# Switch_Board.net
KiCad netlist of a schematic drawn in EAGLE
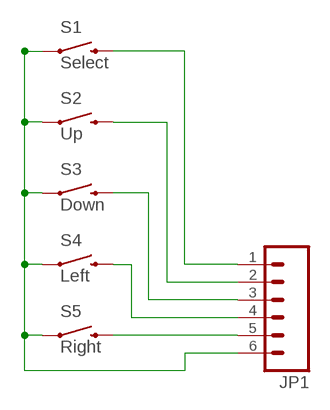
[diagram p0: schematic, sheet 1]

(export (version "E")
  (design (tool "Eeschema 10.0.6"))
  (components
    (comp (ref "JP1")
      (value "M06SMD-1MM")
      (footprint "eagle-import:1X06-1MM")
      (libsource (lib "eagle-import") (part "M06SMD-1MM"))
    )
    (comp (ref "S1")
      (value "Select")
      (footprint "eagle-import:TACTILE-SWITCH-SMD")
      (libsource (lib "eagle-import") (part "SWITCH-MOMENTARY-2SMD"))
    )
    (comp (ref "S2")
      (value "Up")
      (footprint "eagle-import:TACTILE-SWITCH-SMD")
      (libsource (lib "eagle-import") (part "SWITCH-MOMENTARY-2SMD"))
    )
    (comp (ref "S3")
      (value "Down")
      (footprint "eagle-import:TACTILE-SWITCH-SMD")
      (libsource (lib "eagle-import") (part "SWITCH-MOMENTARY-2SMD"))
    )
    (comp (ref "S4")
      (value "Left")
      (footprint "eagle-import:TACTILE-SWITCH-SMD")
      (libsource (lib "eagle-import") (part "SWITCH-MOMENTARY-2SMD"))
    )
    (comp (ref "S5")
      (value "Right")
      (footprint "eagle-import:TACTILE-SWITCH-SMD")
      (libsource (lib "eagle-import") (part "SWITCH-MOMENTARY-2SMD"))
    )
  )
  (nets
    (net (code "1") (name "Net-(JP1-Pad6)") (class "Default")
      (node (ref "JP1") (pin "6") (pinfunction "6_6") (pintype "passive"))
      (node (ref "S1") (pin "1") (pinfunction "1_1") (pintype "passive"))
      (node (ref "S2") (pin "1") (pinfunction "1_1") (pintype "passive"))
      (node (ref "S3") (pin "1") (pinfunction "1_1") (pintype "passive"))
      (node (ref "S4") (pin "1") (pinfunction "1_1") (pintype "passive"))
      (node (ref "S5") (pin "1") (pinfunction "1_1") (pintype "passive"))
    )
    (net (code "2") (name "Net-(S1-2)") (class "Default")
      (node (ref "JP1") (pin "1") (pinfunction "1_1") (pintype "passive"))
      (node (ref "S1") (pin "3") (pinfunction "2_3") (pintype "passive"))
    )
    (net (code "3") (name "Net-(S2-2)") (class "Default")
      (node (ref "JP1") (pin "2") (pinfunction "2_2") (pintype "passive"))
      (node (ref "S2") (pin "3") (pinfunction "2_3") (pintype "passive"))
    )
    (net (code "4") (name "Net-(S3-2)") (class "Default")
      (node (ref "JP1") (pin "3") (pinfunction "3_3") (pintype "passive"))
      (node (ref "S3") (pin "3") (pinfunction "2_3") (pintype "passive"))
    )
    (net (code "5") (name "Net-(S4-2)") (class "Default")
      (node (ref "JP1") (pin "4") (pinfunction "4_4") (pintype "passive"))
      (node (ref "S4") (pin "3") (pinfunction "2_3") (pintype "passive"))
    )
    (net (code "6") (name "Net-(S5-2)") (class "Default")
      (node (ref "JP1") (pin "5") (pinfunction "5_5") (pintype "passive"))
      (node (ref "S5") (pin "3") (pinfunction "2_3") (pintype "passive"))
    )
  )
)
